# RFM69_USB_Gateway_0_7.net
KiCad netlist of a schematic drawn in EAGLE
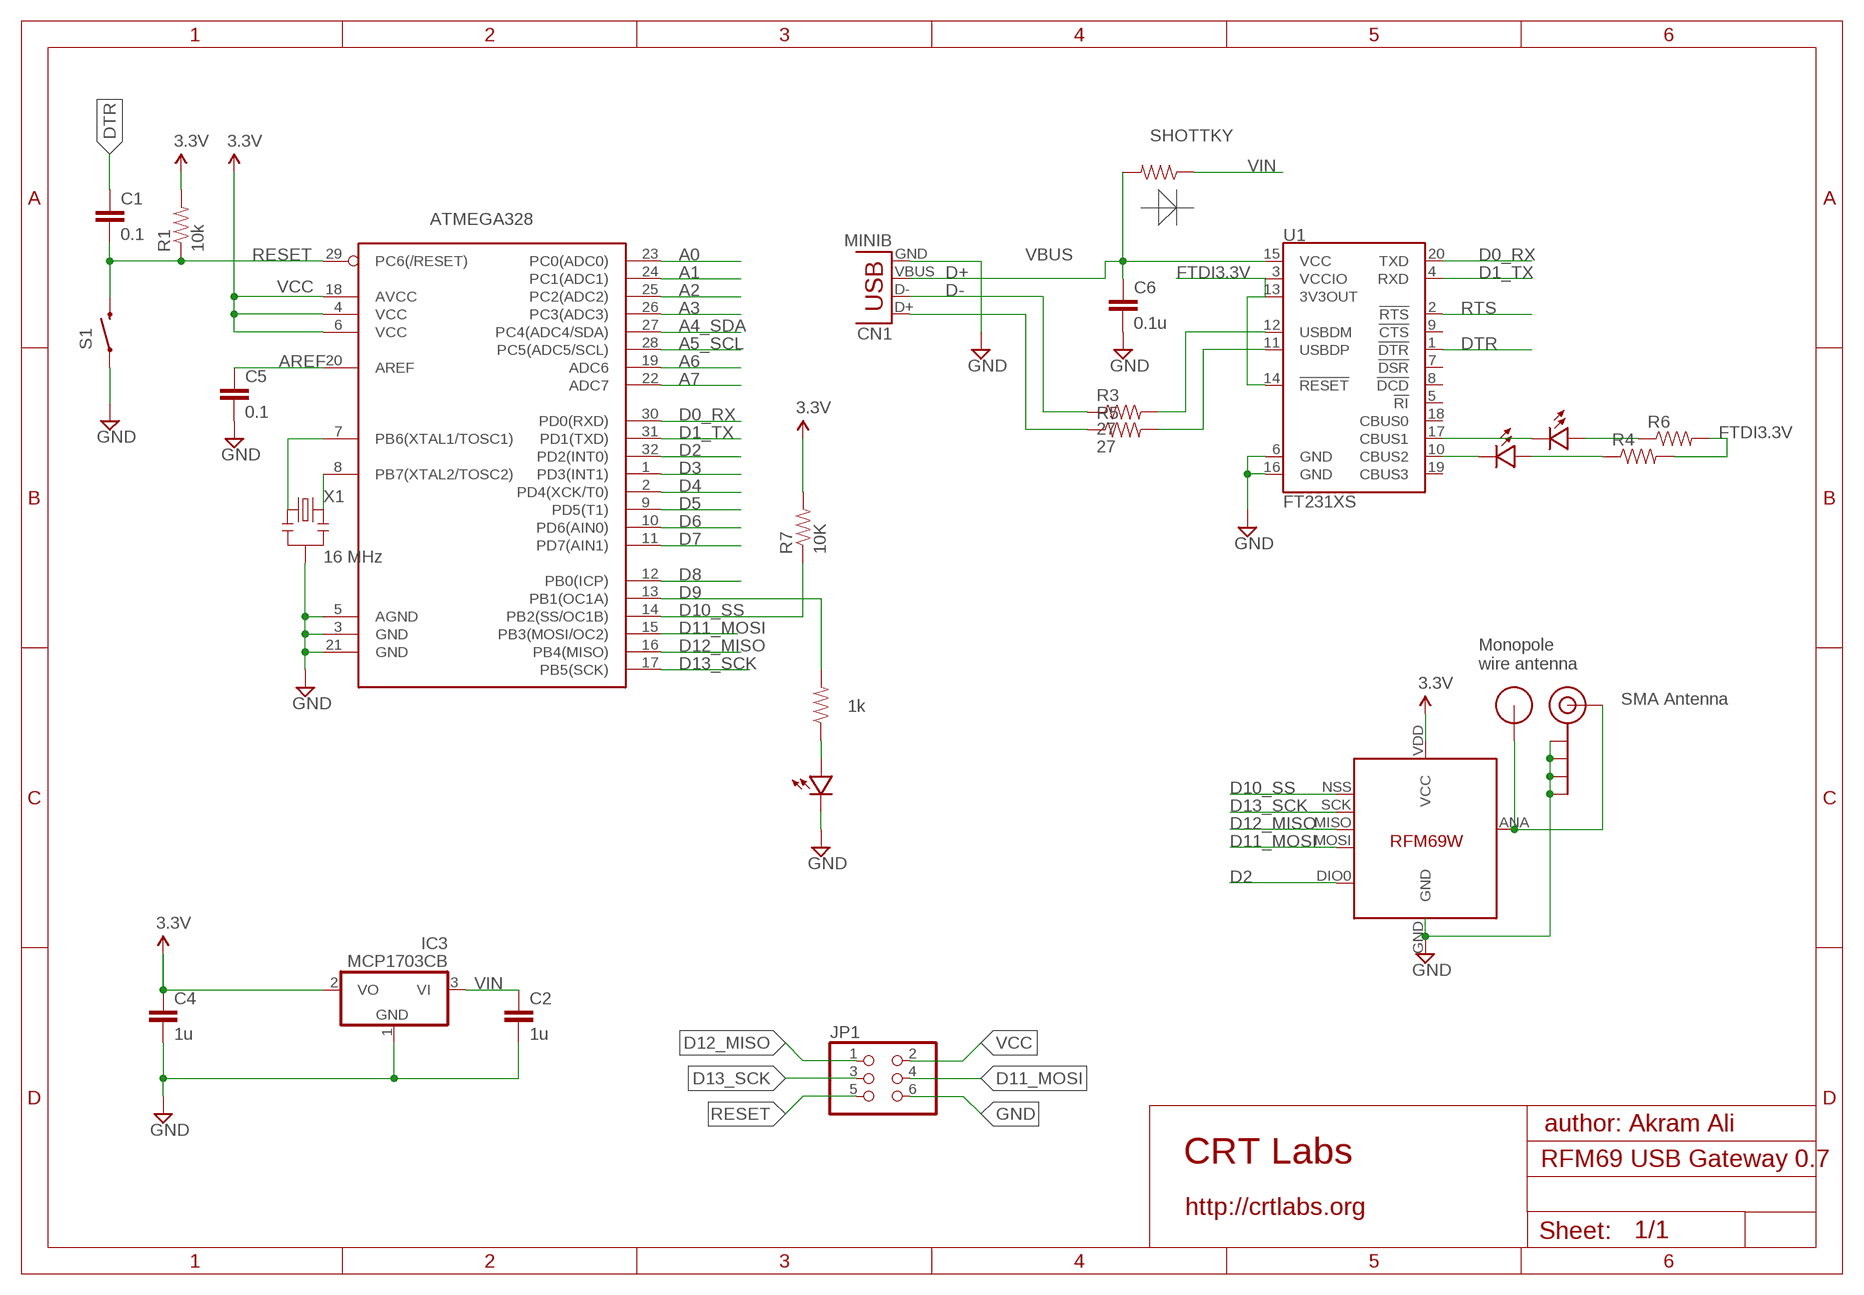
[diagram p0: schematic, sheet 1]

(export (version "E")
  (design (tool "Eeschema 10.0.6"))
  (components
    (comp (ref "ATMEGA328")
      (value "ATMega-328")
      (footprint "eagle-import:TQFP32-08")
      (libsource (lib "eagle-import") (part "ATMEGA168/328TQFP32"))
    )
    (comp (ref "C1")
      (value "0.1")
      (footprint "eagle-import:0805")
      (libsource (lib "eagle-import") (part "SparkFun_CAP0805"))
    )
    (comp (ref "C2")
      (value "1u")
      (footprint "eagle-import:0805")
      (libsource (lib "eagle-import") (part "SparkFun_CAP0805"))
    )
    (comp (ref "C4")
      (value "1u")
      (footprint "eagle-import:0805")
      (libsource (lib "eagle-import") (part "CAP0805"))
    )
    (comp (ref "C5")
      (value "0.1")
      (footprint "eagle-import:0805")
      (libsource (lib "eagle-import") (part "SparkFun_CAP0805"))
    )
    (comp (ref "C6")
      (value "0.1u")
      (footprint "eagle-import:0805")
      (libsource (lib "eagle-import") (part "SparkFun_CAP0805"))
    )
    (comp (ref "CN1")
      (value "MINIB")
      (footprint "eagle-import:USB-A-H")
      (libsource (lib "eagle-import") (part "USB-A-H"))
    )
    (comp (ref "D")
      (value "SHOTTKY")
      (footprint "eagle-import:0805")
      (libsource (lib "eagle-import") (part "RESISTOR0805"))
    )
    (comp (ref "IC3")
      (value "MCP1703CB")
      (footprint "eagle-import:SOT23")
      (libsource (lib "eagle-import") (part "MCP1703CB"))
    )
    (comp (ref "J$1")
      (value "SMA_EDGE")
      (footprint "eagle-import:SMA-EDGE")
      (libsource (lib "eagle-import") (part "SMA_EDGE"))
    )
    (comp (ref "JP1")
      (value "PINHD-2X3")
      (footprint "eagle-import:2X03")
      (libsource (lib "eagle-import") (part "PINHD-2X3"))
    )
    (comp (ref "R1")
      (value "10k")
      (footprint "eagle-import:0805")
      (libsource (lib "eagle-import") (part "RESISTOR0805"))
    )
    (comp (ref "R2")
      (value "1k")
      (footprint "eagle-import:0805")
      (libsource (lib "eagle-import") (part "SparkFun_RESISTOR0805-RES"))
    )
    (comp (ref "R3")
      (value "27")
      (footprint "eagle-import:0805")
      (libsource (lib "eagle-import") (part "SparkFun_RESISTOR0805-RES"))
    )
    (comp (ref "R4")
      (value "RESISTOR0805-RES")
      (footprint "eagle-import:0805")
      (libsource (lib "eagle-import") (part "SparkFun_RESISTOR0805-RES"))
    )
    (comp (ref "R5")
      (value "27")
      (footprint "eagle-import:0805")
      (libsource (lib "eagle-import") (part "SparkFun_RESISTOR0805-RES"))
    )
    (comp (ref "R6")
      (value "RESISTOR0805-RES")
      (footprint "eagle-import:0805")
      (libsource (lib "eagle-import") (part "SparkFun_RESISTOR0805-RES"))
    )
    (comp (ref "R7")
      (value "10K")
      (footprint "eagle-import:0805")
      (libsource (lib "eagle-import") (part "SparkFun_RESISTOR0805-RES"))
    )
    (comp (ref "S1")
      (value "SWITCH-MOMENTARY-2SMD-ALT01")
      (footprint "eagle-import:TACTILE-SWITCH-SMD-ALT01")
      (libsource (lib "eagle-import") (part "SWITCH-MOMENTARY-2SMD-ALT01"))
    )
    (comp (ref "U$1")
      (value "RFM12B_ANTENNA")
      (footprint "eagle-import:RFM12B-ANTENNA")
      (libsource (lib "eagle-import") (part "RFM12B_ANTENNA"))
    )
    (comp (ref "U$2")
      (value "LED0805")
      (footprint "eagle-import:0805-LED")
      (libsource (lib "eagle-import") (part "LED0805"))
    )
    (comp (ref "U$4")
      (value "LED0805")
      (footprint "eagle-import:0805-LED")
      (libsource (lib "eagle-import") (part "LED0805"))
    )
    (comp (ref "U$5")
      (value "RFM69")
      (footprint "eagle-import:RFM69W-MINPADS")
      (libsource (lib "eagle-import") (part "RFM69"))
    )
    (comp (ref "U$7")
      (value "LED0805")
      (footprint "eagle-import:0805-LED")
      (libsource (lib "eagle-import") (part "LED0805"))
    )
    (comp (ref "U1")
      (value "FT231XS")
      (footprint "eagle-import:SSOP20_L")
      (libsource (lib "eagle-import") (part "FT231XS"))
    )
    (comp (ref "X1")
      (value "16 MHz")
      (footprint "eagle-import:RESONATOR-SMD")
      (libsource (lib "eagle-import") (part "RESONATORSMD"))
    )
  )
  (nets
    (net (code "1") (name "/A0") (class "Default")
      (node (ref "ATMEGA328") (pin "23") (pinfunction "PC0(ADC0)_23") (pintype "bidirectional"))
    )
    (net (code "2") (name "/A1") (class "Default")
      (node (ref "ATMEGA328") (pin "24") (pinfunction "PC1(ADC1)_24") (pintype "bidirectional"))
    )
    (net (code "3") (name "/A2") (class "Default")
      (node (ref "ATMEGA328") (pin "25") (pinfunction "PC2(ADC2)_25") (pintype "bidirectional"))
    )
    (net (code "4") (name "/A3") (class "Default")
      (node (ref "ATMEGA328") (pin "26") (pinfunction "PC3(ADC3)_26") (pintype "bidirectional"))
    )
    (net (code "5") (name "/A4_SDA") (class "Default")
      (node (ref "ATMEGA328") (pin "27") (pinfunction "PC4(ADC4/SDA)_27") (pintype "bidirectional"))
    )
    (net (code "6") (name "/A5_SCL") (class "Default")
      (node (ref "ATMEGA328") (pin "28") (pinfunction "PC5(ADC5/SCL)_28") (pintype "bidirectional"))
    )
    (net (code "7") (name "/A6") (class "Default")
      (node (ref "ATMEGA328") (pin "19") (pinfunction "ADC6_19") (pintype "bidirectional"))
    )
    (net (code "8") (name "/A7") (class "Default")
      (node (ref "ATMEGA328") (pin "22") (pinfunction "ADC7_22") (pintype "bidirectional"))
    )
    (net (code "9") (name "/AREF") (class "Default")
      (node (ref "ATMEGA328") (pin "20") (pinfunction "AREF_20") (pintype "bidirectional"))
      (node (ref "C5") (pin "1") (pinfunction "1_1") (pintype "passive"))
    )
    (net (code "10") (name "/D+") (class "Default")
      (node (ref "CN1") (pin "D+") (pinfunction "D+_D+") (pintype "bidirectional"))
      (node (ref "R5") (pin "1") (pinfunction "1_1") (pintype "passive"))
    )
    (net (code "11") (name "/D-") (class "Default")
      (node (ref "CN1") (pin "D-") (pinfunction "D-_D-") (pintype "bidirectional"))
      (node (ref "R3") (pin "1") (pinfunction "1_1") (pintype "passive"))
    )
    (net (code "12") (name "/D0_RX") (class "Default")
      (node (ref "ATMEGA328") (pin "30") (pinfunction "PD0(RXD)_30") (pintype "bidirectional"))
      (node (ref "U1") (pin "20") (pinfunction "TXD_20") (pintype "bidirectional"))
    )
    (net (code "13") (name "/D1_TX") (class "Default")
      (node (ref "ATMEGA328") (pin "31") (pinfunction "PD1(TXD)_31") (pintype "bidirectional"))
      (node (ref "U1") (pin "4") (pinfunction "RXD_4") (pintype "bidirectional"))
    )
    (net (code "14") (name "/D2") (class "Default")
      (node (ref "ATMEGA328") (pin "32") (pinfunction "PD2(INT0)_32") (pintype "bidirectional"))
      (node (ref "U$5") (pin "DIO0") (pinfunction "DIO0_DIO0") (pintype "open_collector"))
    )
    (net (code "15") (name "/D3") (class "Default")
      (node (ref "ATMEGA328") (pin "1") (pinfunction "PD3(INT1)_1") (pintype "bidirectional"))
    )
    (net (code "16") (name "/D4") (class "Default")
      (node (ref "ATMEGA328") (pin "2") (pinfunction "PD4(XCK/T0)_2") (pintype "bidirectional"))
    )
    (net (code "17") (name "/D5") (class "Default")
      (node (ref "ATMEGA328") (pin "9") (pinfunction "PD5(T1)_9") (pintype "bidirectional"))
    )
    (net (code "18") (name "/D6") (class "Default")
      (node (ref "ATMEGA328") (pin "10") (pinfunction "PD6(AIN0)_10") (pintype "bidirectional"))
    )
    (net (code "19") (name "/D7") (class "Default")
      (node (ref "ATMEGA328") (pin "11") (pinfunction "PD7(AIN1)_11") (pintype "bidirectional"))
    )
    (net (code "20") (name "/D8") (class "Default")
      (node (ref "ATMEGA328") (pin "12") (pinfunction "PB0(ICP)_12") (pintype "bidirectional"))
    )
    (net (code "21") (name "/D9") (class "Default")
      (node (ref "ATMEGA328") (pin "13") (pinfunction "PB1(OC1A)_13") (pintype "bidirectional"))
      (node (ref "R2") (pin "2") (pinfunction "2_2") (pintype "passive"))
    )
    (net (code "22") (name "/D10_SS") (class "Default")
      (node (ref "ATMEGA328") (pin "14") (pinfunction "PB2(SS/OC1B)_14") (pintype "bidirectional"))
      (node (ref "R7") (pin "1") (pinfunction "1_1") (pintype "passive"))
      (node (ref "U$5") (pin "NSS") (pinfunction "SEL_NSS") (pintype "input"))
    )
    (net (code "23") (name "/FTDI3.3V") (class "Default")
      (node (ref "R4") (pin "2") (pinfunction "2_2") (pintype "passive"))
      (node (ref "R6") (pin "2") (pinfunction "2_2") (pintype "passive"))
      (node (ref "U1") (pin "13") (pinfunction "3V3OUT_13") (pintype "bidirectional"))
      (node (ref "U1") (pin "14") (pinfunction "~{RESET}_14") (pintype "bidirectional"))
      (node (ref "U1") (pin "3") (pinfunction "VCCIO_3") (pintype "bidirectional"))
    )
    (net (code "24") (name "/RTS") (class "Default")
      (node (ref "U1") (pin "2") (pinfunction "~{RTS}_2") (pintype "bidirectional"))
    )
    (net (code "25") (name "/VBUS") (class "Default")
      (node (ref "C6") (pin "1") (pinfunction "1_1") (pintype "passive"))
      (node (ref "CN1") (pin "VBUS") (pinfunction "VBUS_VBUS") (pintype "bidirectional"))
      (node (ref "D") (pin "2") (pinfunction "2_2") (pintype "passive"))
      (node (ref "U1") (pin "15") (pinfunction "VCC_15") (pintype "bidirectional"))
    )
    (net (code "26") (name "/VIN") (class "Default")
      (node (ref "C2") (pin "1") (pinfunction "1_1") (pintype "passive"))
      (node (ref "D") (pin "1") (pinfunction "1_1") (pintype "passive"))
      (node (ref "IC3") (pin "3") (pinfunction "VI_3") (pintype "input"))
    )
    (net (code "27") (name "D11_MOSI") (class "Default")
      (node (ref "ATMEGA328") (pin "15") (pinfunction "PB3(MOSI/OC2)_15") (pintype "bidirectional"))
      (node (ref "JP1") (pin "4") (pinfunction "4_4") (pintype "passive"))
      (node (ref "U$5") (pin "MOSI") (pinfunction "MOSI_MOSI") (pintype "output"))
    )
    (net (code "28") (name "D12_MISO") (class "Default")
      (node (ref "ATMEGA328") (pin "16") (pinfunction "PB4(MISO)_16") (pintype "bidirectional"))
      (node (ref "JP1") (pin "1") (pinfunction "1_1") (pintype "passive"))
      (node (ref "U$5") (pin "MISO") (pinfunction "MISO_MISO") (pintype "input"))
    )
    (net (code "29") (name "D13_SCK") (class "Default")
      (node (ref "ATMEGA328") (pin "17") (pinfunction "PB5(SCK)_17") (pintype "bidirectional"))
      (node (ref "JP1") (pin "3") (pinfunction "3_3") (pintype "passive"))
      (node (ref "U$5") (pin "SCK") (pinfunction "SCK_SCK") (pintype "input"))
    )
    (net (code "30") (name "DTR") (class "Default")
      (node (ref "C1") (pin "1") (pinfunction "1_1") (pintype "passive"))
      (node (ref "U1") (pin "1") (pinfunction "~{DTR}_1") (pintype "bidirectional"))
    )
    (net (code "31") (name "GND") (class "Default")
      (node (ref "ATMEGA328") (pin "21") (pinfunction "GND_21") (pintype "bidirectional"))
      (node (ref "ATMEGA328") (pin "3") (pinfunction "GND_3") (pintype "bidirectional"))
      (node (ref "ATMEGA328") (pin "5") (pinfunction "AGND_5") (pintype "bidirectional"))
      (node (ref "C2") (pin "2") (pinfunction "2_2") (pintype "passive"))
      (node (ref "C4") (pin "2") (pinfunction "2_2") (pintype "passive"))
      (node (ref "C5") (pin "2") (pinfunction "2_2") (pintype "passive"))
      (node (ref "C6") (pin "2") (pinfunction "2_2") (pintype "passive"))
      (node (ref "CN1") (pin "GND") (pinfunction "GND_GND") (pintype "bidirectional"))
      (node (ref "IC3") (pin "1") (pinfunction "GND_1") (pintype "passive"))
      (node (ref "J$1") (pin "GND@0") (pinfunction "GND_GND@0") (pintype "bidirectional"))
      (node (ref "J$1") (pin "GND@1") (pinfunction "GND_GND@1") (pintype "bidirectional"))
      (node (ref "J$1") (pin "GND@2") (pinfunction "GND_GND@2") (pintype "bidirectional"))
      (node (ref "J$1") (pin "GND@3") (pinfunction "GND_GND@3") (pintype "bidirectional"))
      (node (ref "JP1") (pin "6") (pinfunction "6_6") (pintype "passive"))
      (node (ref "S1") (pin "1") (pinfunction "1_1") (pintype "passive"))
      (node (ref "S1") (pin "2") (pinfunction "1_2") (pintype "passive"))
      (node (ref "U$2") (pin "MINUS") (pinfunction "MINUS_MINUS") (pintype "passive"))
      (node (ref "U$5") (pin "GND") (pinfunction "GND_GND") (pintype "power_in"))
      (node (ref "U1") (pin "16") (pinfunction "GND_16") (pintype "bidirectional"))
      (node (ref "U1") (pin "6") (pinfunction "GND_6") (pintype "bidirectional"))
      (node (ref "X1") (pin "2") (pinfunction "2_2") (pintype "passive"))
    )
    (net (code "32") (name "Net-(ATMEGA328-PB6(XTAL1{slash}TOSC1))") (class "Default")
      (node (ref "ATMEGA328") (pin "7") (pinfunction "PB6(XTAL1/TOSC1)_7") (pintype "bidirectional"))
      (node (ref "X1") (pin "1") (pinfunction "1_1") (pintype "passive"))
    )
    (net (code "33") (name "Net-(ATMEGA328-PB7(XTAL2{slash}TOSC2))") (class "Default")
      (node (ref "ATMEGA328") (pin "8") (pinfunction "PB7(XTAL2/TOSC2)_8") (pintype "bidirectional"))
      (node (ref "X1") (pin "3") (pinfunction "3_3") (pintype "passive"))
    )
    (net (code "34") (name "Net-(J$1-SIGNAL)") (class "Default")
      (node (ref "J$1") (pin "SIG") (pinfunction "SIGNAL_SIG") (pintype "bidirectional"))
      (node (ref "U$1") (pin "P$1") (pinfunction "1_P$1") (pintype "bidirectional"))
      (node (ref "U$5") (pin "ANA") (pinfunction "ANT_ANA") (pintype "passive"))
    )
    (net (code "35") (name "Net-(R2-Pad1)") (class "Default")
      (node (ref "R2") (pin "1") (pinfunction "1_1") (pintype "passive"))
      (node (ref "U$2") (pin "PLUS") (pinfunction "PLUS_PLUS") (pintype "passive"))
    )
    (net (code "36") (name "Net-(R4-Pad1)") (class "Default")
      (node (ref "R4") (pin "1") (pinfunction "1_1") (pintype "passive"))
      (node (ref "U$7") (pin "PLUS") (pinfunction "PLUS_PLUS") (pintype "passive"))
    )
    (net (code "37") (name "Net-(R6-Pad1)") (class "Default")
      (node (ref "R6") (pin "1") (pinfunction "1_1") (pintype "passive"))
      (node (ref "U$4") (pin "PLUS") (pinfunction "PLUS_PLUS") (pintype "passive"))
    )
    (net (code "38") (name "Net-(U1-CBUS1)") (class "Default")
      (node (ref "U$4") (pin "MINUS") (pinfunction "MINUS_MINUS") (pintype "passive"))
      (node (ref "U1") (pin "17") (pinfunction "CBUS1_17") (pintype "bidirectional"))
    )
    (net (code "39") (name "Net-(U1-CBUS2)") (class "Default")
      (node (ref "U$7") (pin "MINUS") (pinfunction "MINUS_MINUS") (pintype "passive"))
      (node (ref "U1") (pin "10") (pinfunction "CBUS2_10") (pintype "bidirectional"))
    )
    (net (code "40") (name "Net-(U1-USBDM)") (class "Default")
      (node (ref "R3") (pin "2") (pinfunction "2_2") (pintype "passive"))
      (node (ref "U1") (pin "12") (pinfunction "USBDM_12") (pintype "bidirectional"))
    )
    (net (code "41") (name "Net-(U1-USBDP)") (class "Default")
      (node (ref "R5") (pin "2") (pinfunction "2_2") (pintype "passive"))
      (node (ref "U1") (pin "11") (pinfunction "USBDP_11") (pintype "bidirectional"))
    )
    (net (code "42") (name "RESET") (class "Default")
      (node (ref "ATMEGA328") (pin "29") (pinfunction "PC6(/RESET)_29") (pintype "bidirectional"))
      (node (ref "C1") (pin "2") (pinfunction "2_2") (pintype "passive"))
      (node (ref "JP1") (pin "5") (pinfunction "5_5") (pintype "passive"))
      (node (ref "R1") (pin "1") (pinfunction "1_1") (pintype "passive"))
      (node (ref "S1") (pin "3") (pinfunction "2_3") (pintype "passive"))
      (node (ref "S1") (pin "4") (pinfunction "2_4") (pintype "passive"))
    )
    (net (code "43") (name "VCC") (class "Default")
      (node (ref "ATMEGA328") (pin "18") (pinfunction "AVCC_18") (pintype "bidirectional"))
      (node (ref "ATMEGA328") (pin "4") (pinfunction "VCC_4") (pintype "bidirectional"))
      (node (ref "ATMEGA328") (pin "6") (pinfunction "VCC_6") (pintype "bidirectional"))
      (node (ref "C4") (pin "1") (pinfunction "1_1") (pintype "passive"))
      (node (ref "IC3") (pin "2") (pinfunction "VO_2") (pintype "passive"))
      (node (ref "JP1") (pin "2") (pinfunction "2_2") (pintype "passive"))
      (node (ref "R1") (pin "2") (pinfunction "2_2") (pintype "passive"))
      (node (ref "R7") (pin "2") (pinfunction "2_2") (pintype "passive"))
      (node (ref "U$5") (pin "VDD") (pinfunction "VCC_VDD") (pintype "power_in"))
    )
    (net (code "44") (name "unconnected-(U1-CBUS0-Pad18)") (class "Default")
      (node (ref "U1") (pin "18") (pinfunction "CBUS0_18") (pintype "bidirectional"))
    )
    (net (code "45") (name "unconnected-(U1-CBUS3-Pad19)") (class "Default")
      (node (ref "U1") (pin "19") (pinfunction "CBUS3_19") (pintype "bidirectional"))
    )
    (net (code "46") (name "unconnected-(U1-~{CTS}-Pad9)") (class "Default")
      (node (ref "U1") (pin "9") (pinfunction "~{CTS}_9") (pintype "bidirectional"))
    )
    (net (code "47") (name "unconnected-(U1-~{DCD}-Pad8)") (class "Default")
      (node (ref "U1") (pin "8") (pinfunction "~{DCD}_8") (pintype "bidirectional"))
    )
    (net (code "48") (name "unconnected-(U1-~{DSR}-Pad7)") (class "Default")
      (node (ref "U1") (pin "7") (pinfunction "~{DSR}_7") (pintype "bidirectional"))
    )
    (net (code "49") (name "unconnected-(U1-~{RI}-Pad5)") (class "Default")
      (node (ref "U1") (pin "5") (pinfunction "~{RI}_5") (pintype "bidirectional"))
    )
  )
)
